# Sch1.net
KiCad netlist of a schematic drawn in EAGLE
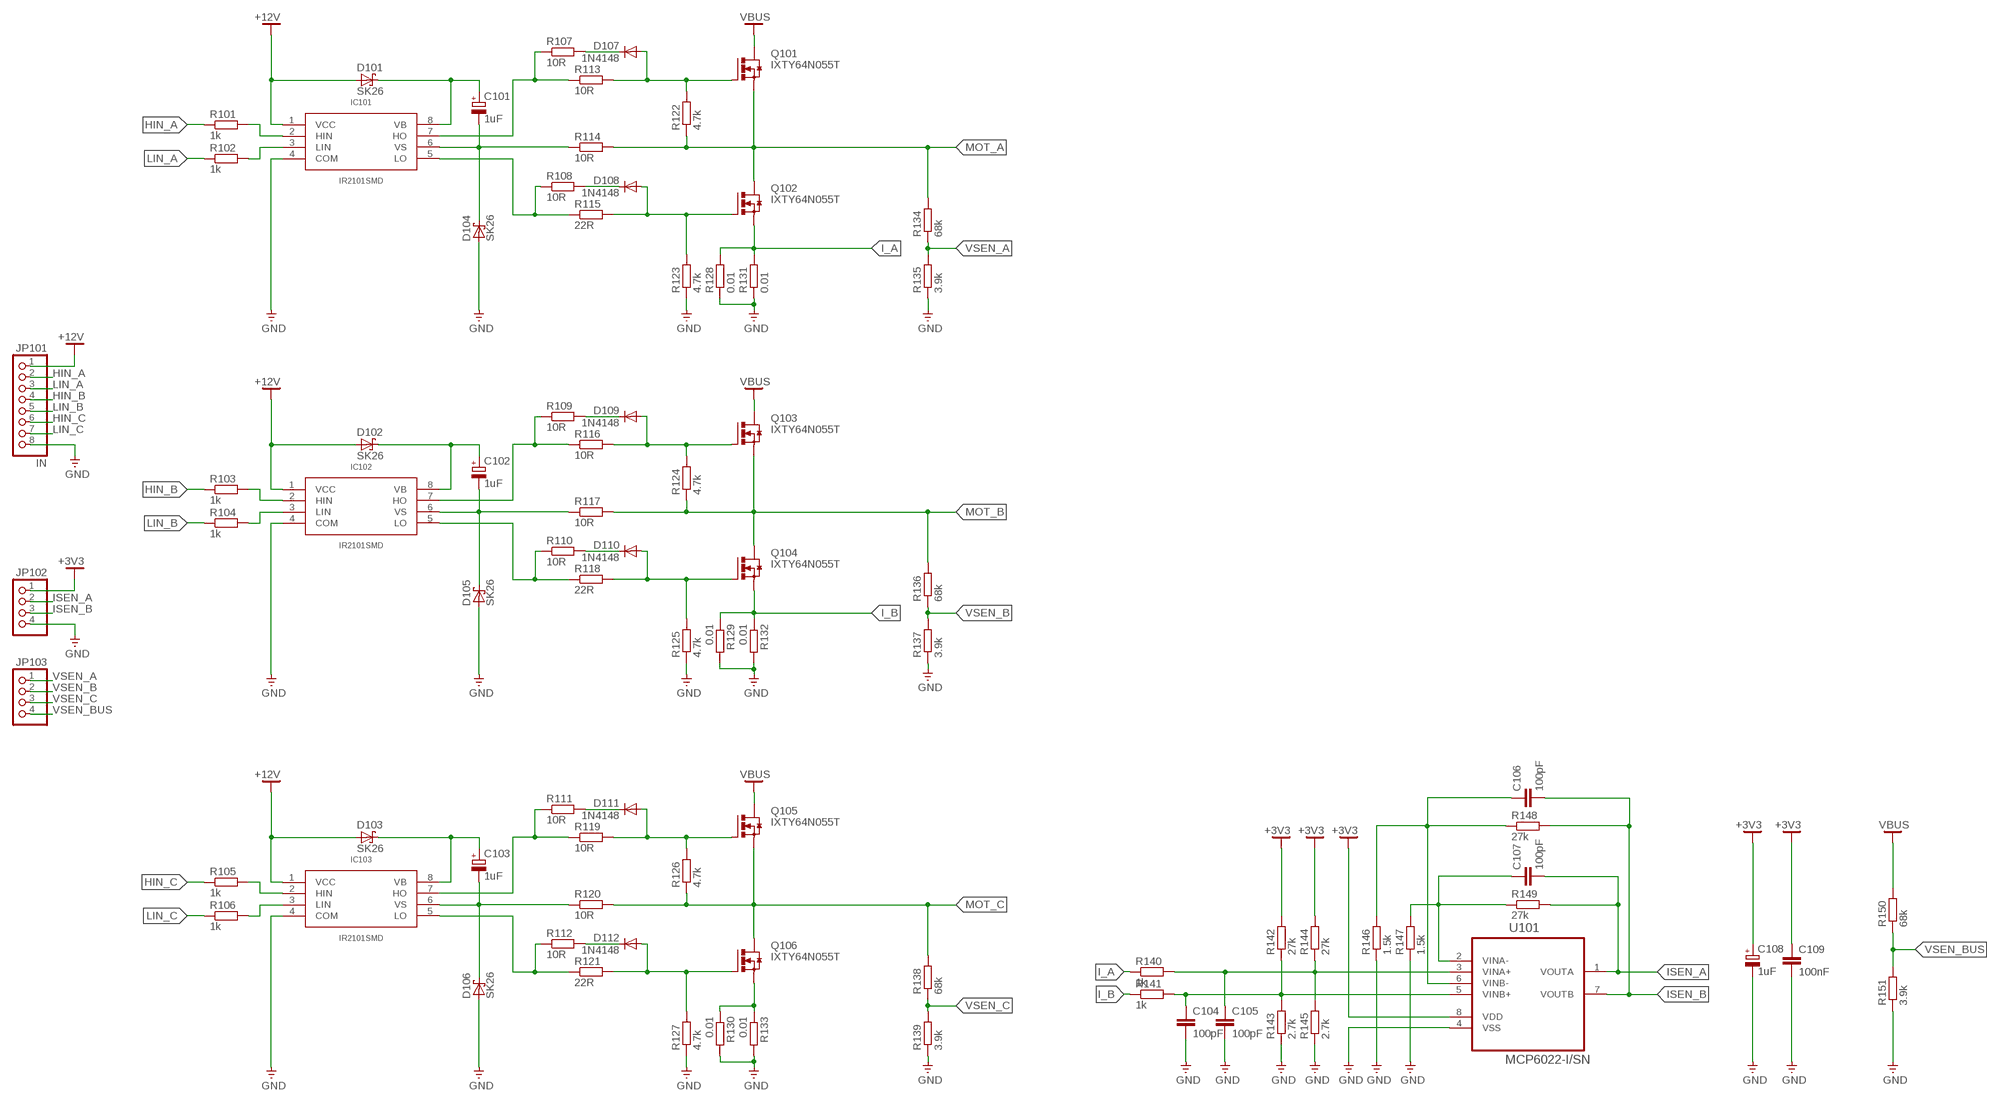
[diagram p0: schematic, sheet 1]

(export (version "E")
  (design (tool "Eeschema 10.0.6"))
  (components
    (comp (ref "C101")
      (value "1uF")
      (footprint "eagle-import:SMC_A")
      (libsource (lib "eagle-import") (part "CPOL-EUSMCA"))
    )
    (comp (ref "C102")
      (value "1uF")
      (footprint "eagle-import:SMC_A")
      (libsource (lib "eagle-import") (part "CPOL-EUSMCA"))
    )
    (comp (ref "C103")
      (value "1uF")
      (footprint "eagle-import:SMC_A")
      (libsource (lib "eagle-import") (part "CPOL-EUSMCA"))
    )
    (comp (ref "C104")
      (value "100pF")
      (footprint "eagle-import:C0805")
      (libsource (lib "eagle-import") (part "C-EUC0805"))
    )
    (comp (ref "C105")
      (value "100pF")
      (footprint "eagle-import:C0805")
      (libsource (lib "eagle-import") (part "C-EUC0805"))
    )
    (comp (ref "C106")
      (value "100pF")
      (footprint "eagle-import:C0805")
      (libsource (lib "eagle-import") (part "C-EUC0805"))
    )
    (comp (ref "C107")
      (value "100pF")
      (footprint "eagle-import:C0805")
      (libsource (lib "eagle-import") (part "C-EUC0805"))
    )
    (comp (ref "C108")
      (value "1uF")
      (footprint "eagle-import:SMC_A")
      (libsource (lib "eagle-import") (part "CPOL-EUSMCA"))
    )
    (comp (ref "C109")
      (value "100nF")
      (footprint "eagle-import:C1206")
      (libsource (lib "eagle-import") (part "C-EUC1206"))
    )
    (comp (ref "D101")
      (value "SK26")
      (footprint "eagle-import:DO214AA")
      (libsource (lib "eagle-import") (part "SCHOTTKY-DIODEDO214AA"))
    )
    (comp (ref "D102")
      (value "SK26")
      (footprint "eagle-import:DO214AA")
      (libsource (lib "eagle-import") (part "SCHOTTKY-DIODEDO214AA"))
    )
    (comp (ref "D103")
      (value "SK26")
      (footprint "eagle-import:DO214AA")
      (libsource (lib "eagle-import") (part "SCHOTTKY-DIODEDO214AA"))
    )
    (comp (ref "D104")
      (value "SK26")
      (footprint "eagle-import:DO214AA")
      (libsource (lib "eagle-import") (part "SCHOTTKY-DIODEDO214AA"))
    )
    (comp (ref "D105")
      (value "SK26")
      (footprint "eagle-import:DO214AA")
      (libsource (lib "eagle-import") (part "SCHOTTKY-DIODEDO214AA"))
    )
    (comp (ref "D106")
      (value "SK26")
      (footprint "eagle-import:DO214AA")
      (libsource (lib "eagle-import") (part "SCHOTTKY-DIODEDO214AA"))
    )
    (comp (ref "D107")
      (value "1N4148")
      (footprint "eagle-import:SOD123FL")
      (libsource (lib "eagle-import") (part "1N4148SOD123"))
    )
    (comp (ref "D108")
      (value "1N4148")
      (footprint "eagle-import:SOD123FL")
      (libsource (lib "eagle-import") (part "1N4148SOD123"))
    )
    (comp (ref "D109")
      (value "1N4148")
      (footprint "eagle-import:SOD123FL")
      (libsource (lib "eagle-import") (part "1N4148SOD123"))
    )
    (comp (ref "D110")
      (value "1N4148")
      (footprint "eagle-import:SOD123FL")
      (libsource (lib "eagle-import") (part "1N4148SOD123"))
    )
    (comp (ref "D111")
      (value "1N4148")
      (footprint "eagle-import:SOD123FL")
      (libsource (lib "eagle-import") (part "1N4148SOD123"))
    )
    (comp (ref "D112")
      (value "1N4148")
      (footprint "eagle-import:SOD123FL")
      (libsource (lib "eagle-import") (part "1N4148SOD123"))
    )
    (comp (ref "IC101")
      (value "IR2101SMD")
      (footprint "eagle-import:SOIC-8")
      (libsource (lib "eagle-import") (part "IR2101SMD"))
    )
    (comp (ref "IC102")
      (value "IR2101SMD")
      (footprint "eagle-import:SOIC-8")
      (libsource (lib "eagle-import") (part "IR2101SMD"))
    )
    (comp (ref "IC103")
      (value "IR2101SMD")
      (footprint "eagle-import:SOIC-8")
      (libsource (lib "eagle-import") (part "IR2101SMD"))
    )
    (comp (ref "JP101")
      (value "IN")
      (footprint "eagle-import:1X08")
      (libsource (lib "eagle-import") (part "PINHD-1X8"))
    )
    (comp (ref "JP102")
      (value "PINHD-1X4")
      (footprint "eagle-import:1X04")
      (libsource (lib "eagle-import") (part "PINHD-1X4"))
    )
    (comp (ref "JP103")
      (value "PINHD-1X4")
      (footprint "eagle-import:1X04")
      (libsource (lib "eagle-import") (part "PINHD-1X4"))
    )
    (comp (ref "Q101")
      (value "IXTY64N055T")
      (footprint "eagle-import:TO252")
      (libsource (lib "eagle-import") (part "IXTY64N055T"))
    )
    (comp (ref "Q102")
      (value "IXTY64N055T")
      (footprint "eagle-import:TO252")
      (libsource (lib "eagle-import") (part "IXTY64N055T"))
    )
    (comp (ref "Q103")
      (value "IXTY64N055T")
      (footprint "eagle-import:TO252")
      (libsource (lib "eagle-import") (part "IXTY64N055T"))
    )
    (comp (ref "Q104")
      (value "IXTY64N055T")
      (footprint "eagle-import:TO252")
      (libsource (lib "eagle-import") (part "IXTY64N055T"))
    )
    (comp (ref "Q105")
      (value "IXTY64N055T")
      (footprint "eagle-import:TO252")
      (libsource (lib "eagle-import") (part "IXTY64N055T"))
    )
    (comp (ref "Q106")
      (value "IXTY64N055T")
      (footprint "eagle-import:TO252")
      (libsource (lib "eagle-import") (part "IXTY64N055T"))
    )
    (comp (ref "R101")
      (value "1k")
      (footprint "eagle-import:R0805")
      (libsource (lib "eagle-import") (part "R-EU_R0805"))
    )
    (comp (ref "R102")
      (value "1k")
      (footprint "eagle-import:R0805")
      (libsource (lib "eagle-import") (part "R-EU_R0805"))
    )
    (comp (ref "R103")
      (value "1k")
      (footprint "eagle-import:R0805")
      (libsource (lib "eagle-import") (part "R-EU_R0805"))
    )
    (comp (ref "R104")
      (value "1k")
      (footprint "eagle-import:R0805")
      (libsource (lib "eagle-import") (part "R-EU_R0805"))
    )
    (comp (ref "R105")
      (value "1k")
      (footprint "eagle-import:R0805")
      (libsource (lib "eagle-import") (part "R-EU_R0805"))
    )
    (comp (ref "R106")
      (value "1k")
      (footprint "eagle-import:R0805")
      (libsource (lib "eagle-import") (part "R-EU_R0805"))
    )
    (comp (ref "R107")
      (value "10R")
      (footprint "eagle-import:R0805")
      (libsource (lib "eagle-import") (part "resistor_R-EU_R0805"))
    )
    (comp (ref "R108")
      (value "10R")
      (footprint "eagle-import:R0805")
      (libsource (lib "eagle-import") (part "resistor_R-EU_R0805"))
    )
    (comp (ref "R109")
      (value "10R")
      (footprint "eagle-import:R0805")
      (libsource (lib "eagle-import") (part "resistor_R-EU_R0805"))
    )
    (comp (ref "R110")
      (value "10R")
      (footprint "eagle-import:R0805")
      (libsource (lib "eagle-import") (part "resistor_R-EU_R0805"))
    )
    (comp (ref "R111")
      (value "10R")
      (footprint "eagle-import:R0805")
      (libsource (lib "eagle-import") (part "resistor_R-EU_R0805"))
    )
    (comp (ref "R112")
      (value "10R")
      (footprint "eagle-import:R0805")
      (libsource (lib "eagle-import") (part "resistor_R-EU_R0805"))
    )
    (comp (ref "R113")
      (value "10R")
      (footprint "eagle-import:R0805")
      (libsource (lib "eagle-import") (part "resistor_R-EU_R0805"))
    )
    (comp (ref "R114")
      (value "10R")
      (footprint "eagle-import:R0805")
      (libsource (lib "eagle-import") (part "resistor_R-EU_R0805"))
    )
    (comp (ref "R115")
      (value "22R")
      (footprint "eagle-import:R0805")
      (libsource (lib "eagle-import") (part "resistor_R-EU_R0805"))
    )
    (comp (ref "R116")
      (value "10R")
      (footprint "eagle-import:R0805")
      (libsource (lib "eagle-import") (part "resistor_R-EU_R0805"))
    )
    (comp (ref "R117")
      (value "10R")
      (footprint "eagle-import:R0805")
      (libsource (lib "eagle-import") (part "resistor_R-EU_R0805"))
    )
    (comp (ref "R118")
      (value "22R")
      (footprint "eagle-import:R0805")
      (libsource (lib "eagle-import") (part "resistor_R-EU_R0805"))
    )
    (comp (ref "R119")
      (value "10R")
      (footprint "eagle-import:R0805")
      (libsource (lib "eagle-import") (part "resistor_R-EU_R0805"))
    )
    (comp (ref "R120")
      (value "10R")
      (footprint "eagle-import:R0805")
      (libsource (lib "eagle-import") (part "resistor_R-EU_R0805"))
    )
    (comp (ref "R121")
      (value "22R")
      (footprint "eagle-import:R0805")
      (libsource (lib "eagle-import") (part "resistor_R-EU_R0805"))
    )
    (comp (ref "R122")
      (value "4.7k")
      (footprint "eagle-import:R0805")
      (libsource (lib "eagle-import") (part "resistor_R-EU_R0805"))
    )
    (comp (ref "R123")
      (value "4.7k")
      (footprint "eagle-import:R0805")
      (libsource (lib "eagle-import") (part "resistor_R-EU_R0805"))
    )
    (comp (ref "R124")
      (value "4.7k")
      (footprint "eagle-import:R0805")
      (libsource (lib "eagle-import") (part "resistor_R-EU_R0805"))
    )
    (comp (ref "R125")
      (value "4.7k")
      (footprint "eagle-import:R0805")
      (libsource (lib "eagle-import") (part "resistor_R-EU_R0805"))
    )
    (comp (ref "R126")
      (value "4.7k")
      (footprint "eagle-import:R0805")
      (libsource (lib "eagle-import") (part "resistor_R-EU_R0805"))
    )
    (comp (ref "R127")
      (value "4.7k")
      (footprint "eagle-import:R0805")
      (libsource (lib "eagle-import") (part "resistor_R-EU_R0805"))
    )
    (comp (ref "R128")
      (value "0.01")
      (footprint "eagle-import:R2512")
      (libsource (lib "eagle-import") (part "R-EU_R2512"))
    )
    (comp (ref "R129")
      (value "0.01")
      (footprint "eagle-import:R2512")
      (libsource (lib "eagle-import") (part "R-EU_R2512"))
    )
    (comp (ref "R130")
      (value "0.01")
      (footprint "eagle-import:R2512")
      (libsource (lib "eagle-import") (part "R-EU_R2512"))
    )
    (comp (ref "R131")
      (value "0.01")
      (footprint "eagle-import:R2512")
      (libsource (lib "eagle-import") (part "R-EU_R2512"))
    )
    (comp (ref "R132")
      (value "0.01")
      (footprint "eagle-import:R2512")
      (libsource (lib "eagle-import") (part "R-EU_R2512"))
    )
    (comp (ref "R133")
      (value "0.01")
      (footprint "eagle-import:R2512")
      (libsource (lib "eagle-import") (part "R-EU_R2512"))
    )
    (comp (ref "R134")
      (value "68k")
      (footprint "eagle-import:R0805")
      (libsource (lib "eagle-import") (part "R-EU_R0805"))
    )
    (comp (ref "R135")
      (value "3.9k")
      (footprint "eagle-import:R0805")
      (libsource (lib "eagle-import") (part "R-EU_R0805"))
    )
    (comp (ref "R136")
      (value "68k")
      (footprint "eagle-import:R0805")
      (libsource (lib "eagle-import") (part "R-EU_R0805"))
    )
    (comp (ref "R137")
      (value "3.9k")
      (footprint "eagle-import:R0805")
      (libsource (lib "eagle-import") (part "R-EU_R0805"))
    )
    (comp (ref "R138")
      (value "68k")
      (footprint "eagle-import:R0805")
      (libsource (lib "eagle-import") (part "R-EU_R0805"))
    )
    (comp (ref "R139")
      (value "3.9k")
      (footprint "eagle-import:R0805")
      (libsource (lib "eagle-import") (part "R-EU_R0805"))
    )
    (comp (ref "R140")
      (value "1k")
      (footprint "eagle-import:R0805")
      (libsource (lib "eagle-import") (part "R-EU_R0805"))
    )
    (comp (ref "R141")
      (value "1k")
      (footprint "eagle-import:R0805")
      (libsource (lib "eagle-import") (part "R-EU_R0805"))
    )
    (comp (ref "R142")
      (value "27k")
      (footprint "eagle-import:R0805")
      (libsource (lib "eagle-import") (part "R-EU_R0805"))
    )
    (comp (ref "R143")
      (value "2.7k")
      (footprint "eagle-import:R0805")
      (libsource (lib "eagle-import") (part "R-EU_R0805"))
    )
    (comp (ref "R144")
      (value "27k")
      (footprint "eagle-import:R0805")
      (libsource (lib "eagle-import") (part "R-EU_R0805"))
    )
    (comp (ref "R145")
      (value "2.7k")
      (footprint "eagle-import:R0805")
      (libsource (lib "eagle-import") (part "R-EU_R0805"))
    )
    (comp (ref "R146")
      (value "1.5k")
      (footprint "eagle-import:R0805")
      (libsource (lib "eagle-import") (part "R-EU_R0805"))
    )
    (comp (ref "R147")
      (value "1.5k")
      (footprint "eagle-import:R0805")
      (libsource (lib "eagle-import") (part "R-EU_R0805"))
    )
    (comp (ref "R148")
      (value "27k")
      (footprint "eagle-import:R0805")
      (libsource (lib "eagle-import") (part "R-EU_R0805"))
    )
    (comp (ref "R149")
      (value "27k")
      (footprint "eagle-import:R0805")
      (libsource (lib "eagle-import") (part "R-EU_R0805"))
    )
    (comp (ref "R150")
      (value "68k")
      (footprint "eagle-import:R0805")
      (libsource (lib "eagle-import") (part "R-EU_R0805"))
    )
    (comp (ref "R151")
      (value "3.9k")
      (footprint "eagle-import:R0805")
      (libsource (lib "eagle-import") (part "R-EU_R0805"))
    )
    (comp (ref "U101")
      (value "MCP6022-I/SN")
      (footprint "eagle-import:SOIC127P600X175-8N")
      (libsource (lib "eagle-import") (part "MCP6022-I/SN"))
    )
  )
  (nets
    (net (code "1") (name "+3V3") (class "Default")
      (node (ref "C108") (pin "+") (pinfunction "+_+") (pintype "passive"))
      (node (ref "C109") (pin "1") (pinfunction "1_1") (pintype "passive"))
      (node (ref "JP102") (pin "1") (pinfunction "1_1") (pintype "passive"))
      (node (ref "R142") (pin "2") (pinfunction "2_2") (pintype "passive"))
      (node (ref "R144") (pin "2") (pinfunction "2_2") (pintype "passive"))
      (node (ref "U101") (pin "8") (pinfunction "VDD_8") (pintype "power_in"))
    )
    (net (code "2") (name "+12V") (class "Default")
      (node (ref "D101") (pin "A") (pinfunction "A_A") (pintype "passive"))
      (node (ref "D102") (pin "A") (pinfunction "A_A") (pintype "passive"))
      (node (ref "D103") (pin "A") (pinfunction "A_A") (pintype "passive"))
      (node (ref "IC101") (pin "1") (pinfunction "VCC_1") (pintype "power_in"))
      (node (ref "IC102") (pin "1") (pinfunction "VCC_1") (pintype "power_in"))
      (node (ref "IC103") (pin "1") (pinfunction "VCC_1") (pintype "power_in"))
      (node (ref "JP101") (pin "1") (pinfunction "1_1") (pintype "passive"))
    )
    (net (code "3") (name "GND") (class "Default")
      (node (ref "C104") (pin "2") (pinfunction "2_2") (pintype "passive"))
      (node (ref "C105") (pin "2") (pinfunction "2_2") (pintype "passive"))
      (node (ref "C108") (pin "-") (pinfunction "-_-") (pintype "passive"))
      (node (ref "C109") (pin "2") (pinfunction "2_2") (pintype "passive"))
      (node (ref "D104") (pin "A") (pinfunction "A_A") (pintype "passive"))
      (node (ref "D105") (pin "A") (pinfunction "A_A") (pintype "passive"))
      (node (ref "D106") (pin "A") (pinfunction "A_A") (pintype "passive"))
      (node (ref "IC101") (pin "4") (pinfunction "COM_4") (pintype "power_in"))
      (node (ref "IC102") (pin "4") (pinfunction "COM_4") (pintype "power_in"))
      (node (ref "IC103") (pin "4") (pinfunction "COM_4") (pintype "power_in"))
      (node (ref "JP101") (pin "8") (pinfunction "8_8") (pintype "passive"))
      (node (ref "JP102") (pin "4") (pinfunction "4_4") (pintype "passive"))
      (node (ref "R123") (pin "1") (pinfunction "1_1") (pintype "passive"))
      (node (ref "R125") (pin "1") (pinfunction "1_1") (pintype "passive"))
      (node (ref "R127") (pin "1") (pinfunction "1_1") (pintype "passive"))
      (node (ref "R128") (pin "1") (pinfunction "1_1") (pintype "passive"))
      (node (ref "R129") (pin "2") (pinfunction "2_2") (pintype "passive"))
      (node (ref "R130") (pin "2") (pinfunction "2_2") (pintype "passive"))
      (node (ref "R131") (pin "1") (pinfunction "1_1") (pintype "passive"))
      (node (ref "R132") (pin "2") (pinfunction "2_2") (pintype "passive"))
      (node (ref "R133") (pin "2") (pinfunction "2_2") (pintype "passive"))
      (node (ref "R135") (pin "1") (pinfunction "1_1") (pintype "passive"))
      (node (ref "R137") (pin "1") (pinfunction "1_1") (pintype "passive"))
      (node (ref "R139") (pin "1") (pinfunction "1_1") (pintype "passive"))
      (node (ref "R143") (pin "1") (pinfunction "1_1") (pintype "passive"))
      (node (ref "R145") (pin "1") (pinfunction "1_1") (pintype "passive"))
      (node (ref "R146") (pin "1") (pinfunction "1_1") (pintype "passive"))
      (node (ref "R147") (pin "1") (pinfunction "1_1") (pintype "passive"))
      (node (ref "R151") (pin "1") (pinfunction "1_1") (pintype "passive"))
      (node (ref "U101") (pin "4") (pinfunction "VSS_4") (pintype "passive"))
    )
    (net (code "4") (name "HIN_A") (class "Default")
      (node (ref "JP101") (pin "2") (pinfunction "2_2") (pintype "passive"))
      (node (ref "R101") (pin "1") (pinfunction "1_1") (pintype "passive"))
    )
    (net (code "5") (name "HIN_B") (class "Default")
      (node (ref "JP101") (pin "4") (pinfunction "4_4") (pintype "passive"))
      (node (ref "R103") (pin "1") (pinfunction "1_1") (pintype "passive"))
    )
    (net (code "6") (name "HIN_C") (class "Default")
      (node (ref "JP101") (pin "6") (pinfunction "6_6") (pintype "passive"))
      (node (ref "R105") (pin "1") (pinfunction "1_1") (pintype "passive"))
    )
    (net (code "7") (name "ISEN_A") (class "Default")
      (node (ref "C107") (pin "2") (pinfunction "2_2") (pintype "passive"))
      (node (ref "JP102") (pin "2") (pinfunction "2_2") (pintype "passive"))
      (node (ref "R149") (pin "2") (pinfunction "2_2") (pintype "passive"))
      (node (ref "U101") (pin "1") (pinfunction "VOUTA_1") (pintype "output"))
    )
    (net (code "8") (name "ISEN_B") (class "Default")
      (node (ref "C106") (pin "2") (pinfunction "2_2") (pintype "passive"))
      (node (ref "JP102") (pin "3") (pinfunction "3_3") (pintype "passive"))
      (node (ref "R148") (pin "2") (pinfunction "2_2") (pintype "passive"))
      (node (ref "U101") (pin "7") (pinfunction "VOUTB_7") (pintype "output"))
    )
    (net (code "9") (name "I_A") (class "Default")
      (node (ref "Q102") (pin "2") (pinfunction "S_2") (pintype "passive"))
      (node (ref "R128") (pin "2") (pinfunction "2_2") (pintype "passive"))
      (node (ref "R131") (pin "2") (pinfunction "2_2") (pintype "passive"))
      (node (ref "R140") (pin "1") (pinfunction "1_1") (pintype "passive"))
    )
    (net (code "10") (name "I_B") (class "Default")
      (node (ref "Q104") (pin "2") (pinfunction "S_2") (pintype "passive"))
      (node (ref "R129") (pin "1") (pinfunction "1_1") (pintype "passive"))
      (node (ref "R132") (pin "1") (pinfunction "1_1") (pintype "passive"))
      (node (ref "R141") (pin "1") (pinfunction "1_1") (pintype "passive"))
    )
    (net (code "11") (name "LIN_A") (class "Default")
      (node (ref "JP101") (pin "3") (pinfunction "3_3") (pintype "passive"))
      (node (ref "R102") (pin "1") (pinfunction "1_1") (pintype "passive"))
    )
    (net (code "12") (name "LIN_B") (class "Default")
      (node (ref "JP101") (pin "5") (pinfunction "5_5") (pintype "passive"))
      (node (ref "R104") (pin "1") (pinfunction "1_1") (pintype "passive"))
    )
    (net (code "13") (name "LIN_C") (class "Default")
      (node (ref "JP101") (pin "7") (pinfunction "7_7") (pintype "passive"))
      (node (ref "R106") (pin "1") (pinfunction "1_1") (pintype "passive"))
    )
    (net (code "14") (name "MOT_A") (class "Default")
      (node (ref "Q101") (pin "2") (pinfunction "S_2") (pintype "passive"))
      (node (ref "Q102") (pin "3") (pinfunction "D_3") (pintype "passive"))
      (node (ref "R114") (pin "2") (pinfunction "2_2") (pintype "passive"))
      (node (ref "R122") (pin "1") (pinfunction "1_1") (pintype "passive"))
      (node (ref "R134") (pin "2") (pinfunction "2_2") (pintype "passive"))
    )
    (net (code "15") (name "MOT_B") (class "Default")
      (node (ref "Q103") (pin "2") (pinfunction "S_2") (pintype "passive"))
      (node (ref "Q104") (pin "3") (pinfunction "D_3") (pintype "passive"))
      (node (ref "R117") (pin "2") (pinfunction "2_2") (pintype "passive"))
      (node (ref "R124") (pin "1") (pinfunction "1_1") (pintype "passive"))
      (node (ref "R136") (pin "2") (pinfunction "2_2") (pintype "passive"))
    )
    (net (code "16") (name "MOT_C") (class "Default")
      (node (ref "Q105") (pin "2") (pinfunction "S_2") (pintype "passive"))
      (node (ref "Q106") (pin "3") (pinfunction "D_3") (pintype "passive"))
      (node (ref "R120") (pin "2") (pinfunction "2_2") (pintype "passive"))
      (node (ref "R126") (pin "1") (pinfunction "1_1") (pintype "passive"))
      (node (ref "R138") (pin "2") (pinfunction "2_2") (pintype "passive"))
    )
    (net (code "17") (name "Net-(D107-PadC)") (class "Default")
      (node (ref "D107") (pin "C") (pinfunction "C_C") (pintype "passive"))
      (node (ref "R107") (pin "2") (pinfunction "2_2") (pintype "passive"))
    )
    (net (code "18") (name "Net-(D108-PadC)") (class "Default")
      (node (ref "D108") (pin "C") (pinfunction "C_C") (pintype "passive"))
      (node (ref "R108") (pin "2") (pinfunction "2_2") (pintype "passive"))
    )
    (net (code "19") (name "Net-(D109-PadC)") (class "Default")
      (node (ref "D109") (pin "C") (pinfunction "C_C") (pintype "passive"))
      (node (ref "R109") (pin "2") (pinfunction "2_2") (pintype "passive"))
    )
    (net (code "20") (name "Net-(D110-PadC)") (class "Default")
      (node (ref "D110") (pin "C") (pinfunction "C_C") (pintype "passive"))
      (node (ref "R110") (pin "2") (pinfunction "2_2") (pintype "passive"))
    )
    (net (code "21") (name "Net-(D111-PadC)") (class "Default")
      (node (ref "D111") (pin "C") (pinfunction "C_C") (pintype "passive"))
      (node (ref "R111") (pin "2") (pinfunction "2_2") (pintype "passive"))
    )
    (net (code "22") (name "Net-(D112-PadC)") (class "Default")
      (node (ref "D112") (pin "C") (pinfunction "C_C") (pintype "passive"))
      (node (ref "R112") (pin "2") (pinfunction "2_2") (pintype "passive"))
    )
    (net (code "23") (name "Net-(IC101-HIN)") (class "Default")
      (node (ref "IC101") (pin "2") (pinfunction "HIN_2") (pintype "input"))
      (node (ref "R101") (pin "2") (pinfunction "2_2") (pintype "passive"))
    )
    (net (code "24") (name "Net-(IC101-HO)") (class "Default")
      (node (ref "IC101") (pin "7") (pinfunction "HO_7") (pintype "output"))
      (node (ref "R107") (pin "1") (pinfunction "1_1") (pintype "passive"))
      (node (ref "R113") (pin "1") (pinfunction "1_1") (pintype "passive"))
    )
    (net (code "25") (name "Net-(IC101-LIN)") (class "Default")
      (node (ref "IC101") (pin "3") (pinfunction "LIN_3") (pintype "input"))
      (node (ref "R102") (pin "2") (pinfunction "2_2") (pintype "passive"))
    )
    (net (code "26") (name "Net-(IC101-LO)") (class "Default")
      (node (ref "IC101") (pin "5") (pinfunction "LO_5") (pintype "output"))
      (node (ref "R108") (pin "1") (pinfunction "1_1") (pintype "passive"))
      (node (ref "R115") (pin "1") (pinfunction "1_1") (pintype "passive"))
    )
    (net (code "27") (name "Net-(IC101-VB)") (class "Default")
      (node (ref "C101") (pin "+") (pinfunction "+_+") (pintype "passive"))
      (node (ref "D101") (pin "C") (pinfunction "C_C") (pintype "passive"))
      (node (ref "IC101") (pin "8") (pinfunction "VB_8") (pintype "power_in"))
    )
    (net (code "28") (name "Net-(IC101-VS)") (class "Default")
      (node (ref "C101") (pin "-") (pinfunction "-_-") (pintype "passive"))
      (node (ref "D104") (pin "C") (pinfunction "C_C") (pintype "passive"))
      (node (ref "IC101") (pin "6") (pinfunction "VS_6") (pintype "power_in"))
      (node (ref "R114") (pin "1") (pinfunction "1_1") (pintype "passive"))
    )
    (net (code "29") (name "Net-(IC102-HIN)") (class "Default")
      (node (ref "IC102") (pin "2") (pinfunction "HIN_2") (pintype "input"))
      (node (ref "R103") (pin "2") (pinfunction "2_2") (pintype "passive"))
    )
    (net (code "30") (name "Net-(IC102-HO)") (class "Default")
      (node (ref "IC102") (pin "7") (pinfunction "HO_7") (pintype "output"))
      (node (ref "R109") (pin "1") (pinfunction "1_1") (pintype "passive"))
      (node (ref "R116") (pin "1") (pinfunction "1_1") (pintype "passive"))
    )
    (net (code "31") (name "Net-(IC102-LIN)") (class "Default")
      (node (ref "IC102") (pin "3") (pinfunction "LIN_3") (pintype "input"))
      (node (ref "R104") (pin "2") (pinfunction "2_2") (pintype "passive"))
    )
    (net (code "32") (name "Net-(IC102-LO)") (class "Default")
      (node (ref "IC102") (pin "5") (pinfunction "LO_5") (pintype "output"))
      (node (ref "R110") (pin "1") (pinfunction "1_1") (pintype "passive"))
      (node (ref "R118") (pin "1") (pinfunction "1_1") (pintype "passive"))
    )
    (net (code "33") (name "Net-(IC102-VB)") (class "Default")
      (node (ref "C102") (pin "+") (pinfunction "+_+") (pintype "passive"))
      (node (ref "D102") (pin "C") (pinfunction "C_C") (pintype "passive"))
      (node (ref "IC102") (pin "8") (pinfunction "VB_8") (pintype "power_in"))
    )
    (net (code "34") (name "Net-(IC102-VS)") (class "Default")
      (node (ref "C102") (pin "-") (pinfunction "-_-") (pintype "passive"))
      (node (ref "D105") (pin "C") (pinfunction "C_C") (pintype "passive"))
      (node (ref "IC102") (pin "6") (pinfunction "VS_6") (pintype "power_in"))
      (node (ref "R117") (pin "1") (pinfunction "1_1") (pintype "passive"))
    )
    (net (code "35") (name "Net-(IC103-HIN)") (class "Default")
      (node (ref "IC103") (pin "2") (pinfunction "HIN_2") (pintype "input"))
      (node (ref "R105") (pin "2") (pinfunction "2_2") (pintype "passive"))
    )
    (net (code "36") (name "Net-(IC103-HO)") (class "Default")
      (node (ref "IC103") (pin "7") (pinfunction "HO_7") (pintype "output"))
      (node (ref "R111") (pin "1") (pinfunction "1_1") (pintype "passive"))
      (node (ref "R119") (pin "1") (pinfunction "1_1") (pintype "passive"))
    )
    (net (code "37") (name "Net-(IC103-LIN)") (class "Default")
      (node (ref "IC103") (pin "3") (pinfunction "LIN_3") (pintype "input"))
      (node (ref "R106") (pin "2") (pinfunction "2_2") (pintype "passive"))
    )
    (net (code "38") (name "Net-(IC103-LO)") (class "Default")
      (node (ref "IC103") (pin "5") (pinfunction "LO_5") (pintype "output"))
      (node (ref "R112") (pin "1") (pinfunction "1_1") (pintype "passive"))
      (node (ref "R121") (pin "1") (pinfunction "1_1") (pintype "passive"))
    )
    (net (code "39") (name "Net-(IC103-VB)") (class "Default")
      (node (ref "C103") (pin "+") (pinfunction "+_+") (pintype "passive"))
      (node (ref "D103") (pin "C") (pinfunction "C_C") (pintype "passive"))
      (node (ref "IC103") (pin "8") (pinfunction "VB_8") (pintype "power_in"))
    )
    (net (code "40") (name "Net-(IC103-VS)") (class "Default")
      (node (ref "C103") (pin "-") (pinfunction "-_-") (pintype "passive"))
      (node (ref "D106") (pin "C") (pinfunction "C_C") (pintype "passive"))
      (node (ref "IC103") (pin "6") (pinfunction "VS_6") (pintype "power_in"))
      (node (ref "R120") (pin "1") (pinfunction "1_1") (pintype "passive"))
    )
    (net (code "41") (name "Net-(Q101-G)") (class "Default")
      (node (ref "D107") (pin "A") (pinfunction "A_A") (pintype "passive"))
      (node (ref "Q101") (pin "1") (pinfunction "G_1") (pintype "passive"))
      (node (ref "R113") (pin "2") (pinfunction "2_2") (pintype "passive"))
      (node (ref "R122") (pin "2") (pinfunction "2_2") (pintype "passive"))
    )
    (net (code "42") (name "Net-(Q102-G)") (class "Default")
      (node (ref "D108") (pin "A") (pinfunction "A_A") (pintype "passive"))
      (node (ref "Q102") (pin "1") (pinfunction "G_1") (pintype "passive"))
      (node (ref "R115") (pin "2") (pinfunction "2_2") (pintype "passive"))
      (node (ref "R123") (pin "2") (pinfunction "2_2") (pintype "passive"))
    )
    (net (code "43") (name "Net-(Q103-G)") (class "Default")
      (node (ref "D109") (pin "A") (pinfunction "A_A") (pintype "passive"))
      (node (ref "Q103") (pin "1") (pinfunction "G_1") (pintype "passive"))
      (node (ref "R116") (pin "2") (pinfunction "2_2") (pintype "passive"))
      (node (ref "R124") (pin "2") (pinfunction "2_2") (pintype "passive"))
    )
    (net (code "44") (name "Net-(Q104-G)") (class "Default")
      (node (ref "D110") (pin "A") (pinfunction "A_A") (pintype "passive"))
      (node (ref "Q104") (pin "1") (pinfunction "G_1") (pintype "passive"))
      (node (ref "R118") (pin "2") (pinfunction "2_2") (pintype "passive"))
      (node (ref "R125") (pin "2") (pinfunction "2_2") (pintype "passive"))
    )
    (net (code "45") (name "Net-(Q105-G)") (class "Default")
      (node (ref "D111") (pin "A") (pinfunction "A_A") (pintype "passive"))
      (node (ref "Q105") (pin "1") (pinfunction "G_1") (pintype "passive"))
      (node (ref "R119") (pin "2") (pinfunction "2_2") (pintype "passive"))
      (node (ref "R126") (pin "2") (pinfunction "2_2") (pintype "passive"))
    )
    (net (code "46") (name "Net-(Q106-G)") (class "Default")
      (node (ref "D112") (pin "A") (pinfunction "A_A") (pintype "passive"))
      (node (ref "Q106") (pin "1") (pinfunction "G_1") (pintype "passive"))
      (node (ref "R121") (pin "2") (pinfunction "2_2") (pintype "passive"))
      (node (ref "R127") (pin "2") (pinfunction "2_2") (pintype "passive"))
    )
    (net (code "47") (name "Net-(Q106-S)") (class "Default")
      (node (ref "Q106") (pin "2") (pinfunction "S_2") (pintype "passive"))
      (node (ref "R130") (pin "1") (pinfunction "1_1") (pintype "passive"))
      (node (ref "R133") (pin "1") (pinfunction "1_1") (pintype "passive"))
    )
    (net (code "48") (name "Net-(U101-VINA+)") (class "Default")
      (node (ref "C105") (pin "1") (pinfunction "1_1") (pintype "passive"))
      (node (ref "R140") (pin "2") (pinfunction "2_2") (pintype "passive"))
      (node (ref "R144") (pin "1") (pinfunction "1_1") (pintype "passive"))
      (node (ref "R145") (pin "2") (pinfunction "2_2") (pintype "passive"))
      (node (ref "U101") (pin "3") (pinfunction "VINA+_3") (pintype "input"))
    )
    (net (code "49") (name "Net-(U101-VINA-)") (class "Default")
      (node (ref "C107") (pin "1") (pinfunction "1_1") (pintype "passive"))
      (node (ref "R147") (pin "2") (pinfunction "2_2") (pintype "passive"))
      (node (ref "R149") (pin "1") (pinfunction "1_1") (pintype "passive"))
      (node (ref "U101") (pin "2") (pinfunction "VINA-_2") (pintype "input"))
    )
    (net (code "50") (name "Net-(U101-VINB+)") (class "Default")
      (node (ref "C104") (pin "1") (pinfunction "1_1") (pintype "passive"))
      (node (ref "R141") (pin "2") (pinfunction "2_2") (pintype "passive"))
      (node (ref "R142") (pin "1") (pinfunction "1_1") (pintype "passive"))
      (node (ref "R143") (pin "2") (pinfunction "2_2") (pintype "passive"))
      (node (ref "U101") (pin "5") (pinfunction "VINB+_5") (pintype "input"))
    )
    (net (code "51") (name "Net-(U101-VINB-)") (class "Default")
      (node (ref "C106") (pin "1") (pinfunction "1_1") (pintype "passive"))
      (node (ref "R146") (pin "2") (pinfunction "2_2") (pintype "passive"))
      (node (ref "R148") (pin "1") (pinfunction "1_1") (pintype "passive"))
      (node (ref "U101") (pin "6") (pinfunction "VINB-_6") (pintype "input"))
    )
    (net (code "52") (name "VBUS") (class "Default")
      (node (ref "Q101") (pin "3") (pinfunction "D_3") (pintype "passive"))
      (node (ref "Q103") (pin "3") (pinfunction "D_3") (pintype "passive"))
      (node (ref "Q105") (pin "3") (pinfunction "D_3") (pintype "passive"))
      (node (ref "R150") (pin "2") (pinfunction "2_2") (pintype "passive"))
    )
    (net (code "53") (name "VSEN_A") (class "Default")
      (node (ref "JP103") (pin "1") (pinfunction "1_1") (pintype "passive"))
      (node (ref "R134") (pin "1") (pinfunction "1_1") (pintype "passive"))
      (node (ref "R135") (pin "2") (pinfunction "2_2") (pintype "passive"))
    )
    (net (code "54") (name "VSEN_B") (class "Default")
      (node (ref "JP103") (pin "2") (pinfunction "2_2") (pintype "passive"))
      (node (ref "R136") (pin "1") (pinfunction "1_1") (pintype "passive"))
      (node (ref "R137") (pin "2") (pinfunction "2_2") (pintype "passive"))
    )
    (net (code "55") (name "VSEN_BUS") (class "Default")
      (node (ref "JP103") (pin "4") (pinfunction "4_4") (pintype "passive"))
      (node (ref "R150") (pin "1") (pinfunction "1_1") (pintype "passive"))
      (node (ref "R151") (pin "2") (pinfunction "2_2") (pintype "passive"))
    )
    (net (code "56") (name "VSEN_C") (class "Default")
      (node (ref "JP103") (pin "3") (pinfunction "3_3") (pintype "passive"))
      (node (ref "R138") (pin "1") (pinfunction "1_1") (pintype "passive"))
      (node (ref "R139") (pin "2") (pinfunction "2_2") (pintype "passive"))
    )
  )
)
